# relays.net
KiCad netlist of a schematic drawn in EAGLE
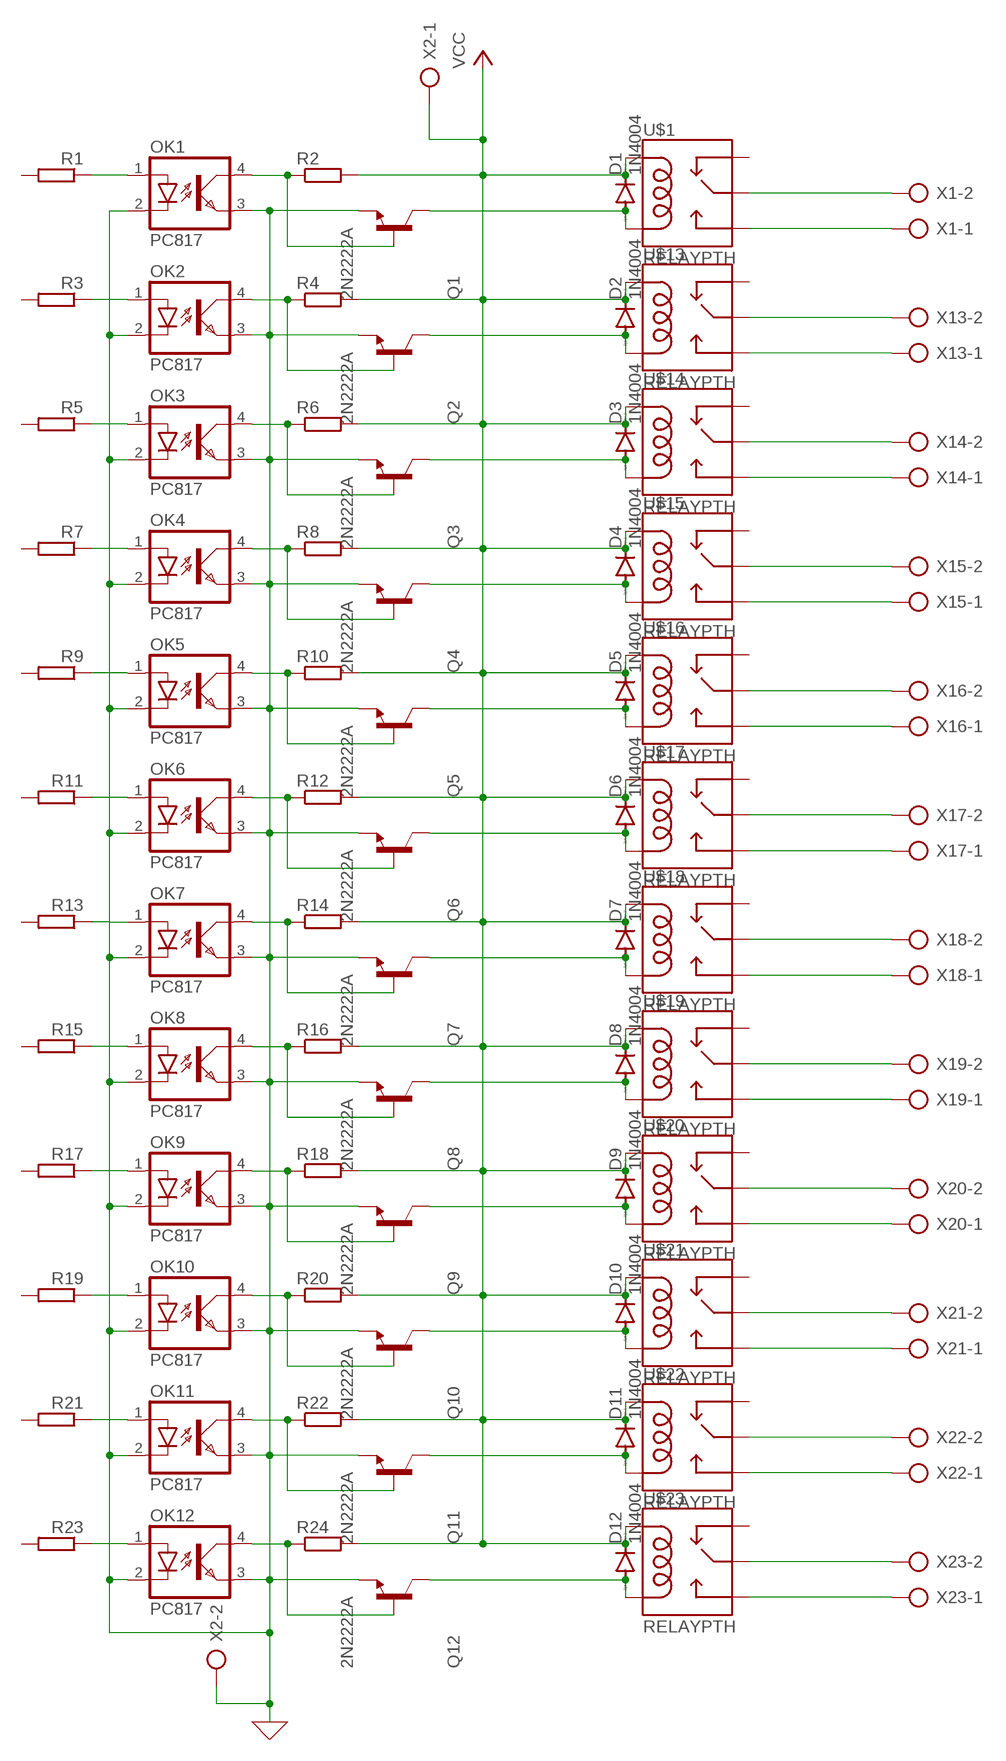
[diagram p0: schematic, sheet 1]

(export (version "E")
  (design (tool "Eeschema 10.0.6"))
  (components
    (comp (ref "D1")
      (value "1N4004")
      (footprint "eagle-import:DO41-10")
      (libsource (lib "eagle-import") (part "1N4004"))
    )
    (comp (ref "D2")
      (value "1N4004")
      (footprint "eagle-import:DO41-10")
      (libsource (lib "eagle-import") (part "1N4004"))
    )
    (comp (ref "D3")
      (value "1N4004")
      (footprint "eagle-import:DO41-10")
      (libsource (lib "eagle-import") (part "1N4004"))
    )
    (comp (ref "D4")
      (value "1N4004")
      (footprint "eagle-import:DO41-10")
      (libsource (lib "eagle-import") (part "1N4004"))
    )
    (comp (ref "D5")
      (value "1N4004")
      (footprint "eagle-import:DO41-10")
      (libsource (lib "eagle-import") (part "1N4004"))
    )
    (comp (ref "D6")
      (value "1N4004")
      (footprint "eagle-import:DO41-10")
      (libsource (lib "eagle-import") (part "1N4004"))
    )
    (comp (ref "D7")
      (value "1N4004")
      (footprint "eagle-import:DO41-10")
      (libsource (lib "eagle-import") (part "1N4004"))
    )
    (comp (ref "D8")
      (value "1N4004")
      (footprint "eagle-import:DO41-10")
      (libsource (lib "eagle-import") (part "1N4004"))
    )
    (comp (ref "D9")
      (value "1N4004")
      (footprint "eagle-import:DO41-10")
      (libsource (lib "eagle-import") (part "1N4004"))
    )
    (comp (ref "D10")
      (value "1N4004")
      (footprint "eagle-import:DO41-10")
      (libsource (lib "eagle-import") (part "1N4004"))
    )
    (comp (ref "D11")
      (value "1N4004")
      (footprint "eagle-import:DO41-10")
      (libsource (lib "eagle-import") (part "1N4004"))
    )
    (comp (ref "D12")
      (value "1N4004")
      (footprint "eagle-import:DO41-10")
      (libsource (lib "eagle-import") (part "1N4004"))
    )
    (comp (ref "OK1")
      (value "PC817")
      (footprint "eagle-import:DIL04")
      (fields (field (name "MPN") "PC817X4J000F"))
      (libsource (lib "eagle-import") (part "PC817"))
    )
    (comp (ref "OK2")
      (value "PC817")
      (footprint "eagle-import:DIL04")
      (fields (field (name "MPN") "PC817X4J000F"))
      (libsource (lib "eagle-import") (part "PC817"))
    )
    (comp (ref "OK3")
      (value "PC817")
      (footprint "eagle-import:DIL04")
      (fields (field (name "MPN") "PC817X4J000F"))
      (libsource (lib "eagle-import") (part "PC817"))
    )
    (comp (ref "OK4")
      (value "PC817")
      (footprint "eagle-import:DIL04")
      (fields (field (name "MPN") "PC817X4J000F"))
      (libsource (lib "eagle-import") (part "PC817"))
    )
    (comp (ref "OK5")
      (value "PC817")
      (footprint "eagle-import:DIL04")
      (fields (field (name "MPN") "PC817X4J000F"))
      (libsource (lib "eagle-import") (part "PC817"))
    )
    (comp (ref "OK6")
      (value "PC817")
      (footprint "eagle-import:DIL04")
      (fields (field (name "MPN") "PC817X4J000F"))
      (libsource (lib "eagle-import") (part "PC817"))
    )
    (comp (ref "OK7")
      (value "PC817")
      (footprint "eagle-import:DIL04")
      (fields (field (name "MPN") "PC817X4J000F"))
      (libsource (lib "eagle-import") (part "PC817"))
    )
    (comp (ref "OK8")
      (value "PC817")
      (footprint "eagle-import:DIL04")
      (fields (field (name "MPN") "PC817X4J000F"))
      (libsource (lib "eagle-import") (part "PC817"))
    )
    (comp (ref "OK9")
      (value "PC817")
      (footprint "eagle-import:DIL04")
      (fields (field (name "MPN") "PC817X4J000F"))
      (libsource (lib "eagle-import") (part "PC817"))
    )
    (comp (ref "OK10")
      (value "PC817")
      (footprint "eagle-import:DIL04")
      (fields (field (name "MPN") "PC817X4J000F"))
      (libsource (lib "eagle-import") (part "PC817"))
    )
    (comp (ref "OK11")
      (value "PC817")
      (footprint "eagle-import:DIL04")
      (fields (field (name "MPN") "PC817X4J000F"))
      (libsource (lib "eagle-import") (part "PC817"))
    )
    (comp (ref "OK12")
      (value "PC817")
      (footprint "eagle-import:DIL04")
      (fields (field (name "MPN") "PC817X4J000F"))
      (libsource (lib "eagle-import") (part "PC817"))
    )
    (comp (ref "Q1")
      (value "2N2222A")
      (footprint "eagle-import:TO92254P470H750-3")
      (fields (field (name "MF") "Diotec Semiconductor"))
      (libsource (lib "eagle-import") (part "2N2222A"))
    )
    (comp (ref "Q2")
      (value "2N2222A")
      (footprint "eagle-import:TO92254P470H750-3")
      (fields (field (name "MF") "Diotec Semiconductor"))
      (libsource (lib "eagle-import") (part "2N2222A"))
    )
    (comp (ref "Q3")
      (value "2N2222A")
      (footprint "eagle-import:TO92254P470H750-3")
      (fields (field (name "MF") "Diotec Semiconductor"))
      (libsource (lib "eagle-import") (part "2N2222A"))
    )
    (comp (ref "Q4")
      (value "2N2222A")
      (footprint "eagle-import:TO92254P470H750-3")
      (fields (field (name "MF") "Diotec Semiconductor"))
      (libsource (lib "eagle-import") (part "2N2222A"))
    )
    (comp (ref "Q5")
      (value "2N2222A")
      (footprint "eagle-import:TO92254P470H750-3")
      (fields (field (name "MF") "Diotec Semiconductor"))
      (libsource (lib "eagle-import") (part "2N2222A"))
    )
    (comp (ref "Q6")
      (value "2N2222A")
      (footprint "eagle-import:TO92254P470H750-3")
      (fields (field (name "MF") "Diotec Semiconductor"))
      (libsource (lib "eagle-import") (part "2N2222A"))
    )
    (comp (ref "Q7")
      (value "2N2222A")
      (footprint "eagle-import:TO92254P470H750-3")
      (fields (field (name "MF") "Diotec Semiconductor"))
      (libsource (lib "eagle-import") (part "2N2222A"))
    )
    (comp (ref "Q8")
      (value "2N2222A")
      (footprint "eagle-import:TO92254P470H750-3")
      (fields (field (name "MF") "Diotec Semiconductor"))
      (libsource (lib "eagle-import") (part "2N2222A"))
    )
    (comp (ref "Q9")
      (value "2N2222A")
      (footprint "eagle-import:TO92254P470H750-3")
      (fields (field (name "MF") "Diotec Semiconductor"))
      (libsource (lib "eagle-import") (part "2N2222A"))
    )
    (comp (ref "Q10")
      (value "2N2222A")
      (footprint "eagle-import:TO92254P470H750-3")
      (fields (field (name "MF") "Diotec Semiconductor"))
      (libsource (lib "eagle-import") (part "2N2222A"))
    )
    (comp (ref "Q11")
      (value "2N2222A")
      (footprint "eagle-import:TO92254P470H750-3")
      (fields (field (name "MF") "Diotec Semiconductor"))
      (libsource (lib "eagle-import") (part "2N2222A"))
    )
    (comp (ref "Q12")
      (value "2N2222A")
      (footprint "eagle-import:TO92254P470H750-3")
      (fields (field (name "MF") "Diotec Semiconductor"))
      (libsource (lib "eagle-import") (part "2N2222A"))
    )
    (comp (ref "R1")
      (value "R-EU_0309/12")
      (footprint "eagle-import:0309_12")
      (libsource (lib "eagle-import") (part "R-EU_0309/12"))
    )
    (comp (ref "R2")
      (value "R-EU_0309/12")
      (footprint "eagle-import:0309_12")
      (libsource (lib "eagle-import") (part "R-EU_0309/12"))
    )
    (comp (ref "R3")
      (value "R-EU_0309/12")
      (footprint "eagle-import:0309_12")
      (libsource (lib "eagle-import") (part "R-EU_0309/12"))
    )
    (comp (ref "R4")
      (value "R-EU_0309/12")
      (footprint "eagle-import:0309_12")
      (libsource (lib "eagle-import") (part "R-EU_0309/12"))
    )
    (comp (ref "R5")
      (value "R-EU_0309/12")
      (footprint "eagle-import:0309_12")
      (libsource (lib "eagle-import") (part "R-EU_0309/12"))
    )
    (comp (ref "R6")
      (value "R-EU_0309/12")
      (footprint "eagle-import:0309_12")
      (libsource (lib "eagle-import") (part "R-EU_0309/12"))
    )
    (comp (ref "R7")
      (value "R-EU_0309/12")
      (footprint "eagle-import:0309_12")
      (libsource (lib "eagle-import") (part "R-EU_0309/12"))
    )
    (comp (ref "R8")
      (value "R-EU_0309/12")
      (footprint "eagle-import:0309_12")
      (libsource (lib "eagle-import") (part "R-EU_0309/12"))
    )
    (comp (ref "R9")
      (value "R-EU_0309/12")
      (footprint "eagle-import:0309_12")
      (libsource (lib "eagle-import") (part "R-EU_0309/12"))
    )
    (comp (ref "R10")
      (value "R-EU_0309/12")
      (footprint "eagle-import:0309_12")
      (libsource (lib "eagle-import") (part "R-EU_0309/12"))
    )
    (comp (ref "R11")
      (value "R-EU_0309/12")
      (footprint "eagle-import:0309_12")
      (libsource (lib "eagle-import") (part "R-EU_0309/12"))
    )
    (comp (ref "R12")
      (value "R-EU_0309/12")
      (footprint "eagle-import:0309_12")
      (libsource (lib "eagle-import") (part "R-EU_0309/12"))
    )
    (comp (ref "R13")
      (value "R-EU_0309/12")
      (footprint "eagle-import:0309_12")
      (libsource (lib "eagle-import") (part "R-EU_0309/12"))
    )
    (comp (ref "R14")
      (value "R-EU_0309/12")
      (footprint "eagle-import:0309_12")
      (libsource (lib "eagle-import") (part "R-EU_0309/12"))
    )
    (comp (ref "R15")
      (value "R-EU_0309/12")
      (footprint "eagle-import:0309_12")
      (libsource (lib "eagle-import") (part "R-EU_0309/12"))
    )
    (comp (ref "R16")
      (value "R-EU_0309/12")
      (footprint "eagle-import:0309_12")
      (libsource (lib "eagle-import") (part "R-EU_0309/12"))
    )
    (comp (ref "R17")
      (value "R-EU_0309/12")
      (footprint "eagle-import:0309_12")
      (libsource (lib "eagle-import") (part "R-EU_0309/12"))
    )
    (comp (ref "R18")
      (value "R-EU_0309/12")
      (footprint "eagle-import:0309_12")
      (libsource (lib "eagle-import") (part "R-EU_0309/12"))
    )
    (comp (ref "R19")
      (value "R-EU_0309/12")
      (footprint "eagle-import:0309_12")
      (libsource (lib "eagle-import") (part "R-EU_0309/12"))
    )
    (comp (ref "R20")
      (value "R-EU_0309/12")
      (footprint "eagle-import:0309_12")
      (libsource (lib "eagle-import") (part "R-EU_0309/12"))
    )
    (comp (ref "R21")
      (value "R-EU_0309/12")
      (footprint "eagle-import:0309_12")
      (libsource (lib "eagle-import") (part "R-EU_0309/12"))
    )
    (comp (ref "R22")
      (value "R-EU_0309/12")
      (footprint "eagle-import:0309_12")
      (libsource (lib "eagle-import") (part "R-EU_0309/12"))
    )
    (comp (ref "R23")
      (value "R-EU_0309/12")
      (footprint "eagle-import:0309_12")
      (libsource (lib "eagle-import") (part "R-EU_0309/12"))
    )
    (comp (ref "R24")
      (value "R-EU_0309/12")
      (footprint "eagle-import:0309_12")
      (libsource (lib "eagle-import") (part "R-EU_0309/12"))
    )
    (comp (ref "U$1")
      (value "RELAYPTH")
      (footprint "eagle-import:SRD-05VDC-SL-C")
      (libsource (lib "eagle-import") (part "RELAYPTH"))
    )
    (comp (ref "U$13")
      (value "RELAYPTH")
      (footprint "eagle-import:SRD-05VDC-SL-C")
      (libsource (lib "eagle-import") (part "RELAYPTH"))
    )
    (comp (ref "U$14")
      (value "RELAYPTH")
      (footprint "eagle-import:SRD-05VDC-SL-C")
      (libsource (lib "eagle-import") (part "RELAYPTH"))
    )
    (comp (ref "U$15")
      (value "RELAYPTH")
      (footprint "eagle-import:SRD-05VDC-SL-C")
      (libsource (lib "eagle-import") (part "RELAYPTH"))
    )
    (comp (ref "U$16")
      (value "RELAYPTH")
      (footprint "eagle-import:SRD-05VDC-SL-C")
      (libsource (lib "eagle-import") (part "RELAYPTH"))
    )
    (comp (ref "U$17")
      (value "RELAYPTH")
      (footprint "eagle-import:SRD-05VDC-SL-C")
      (libsource (lib "eagle-import") (part "RELAYPTH"))
    )
    (comp (ref "U$18")
      (value "RELAYPTH")
      (footprint "eagle-import:SRD-05VDC-SL-C")
      (libsource (lib "eagle-import") (part "RELAYPTH"))
    )
    (comp (ref "U$19")
      (value "RELAYPTH")
      (footprint "eagle-import:SRD-05VDC-SL-C")
      (libsource (lib "eagle-import") (part "RELAYPTH"))
    )
    (comp (ref "U$20")
      (value "RELAYPTH")
      (footprint "eagle-import:SRD-05VDC-SL-C")
      (libsource (lib "eagle-import") (part "RELAYPTH"))
    )
    (comp (ref "U$21")
      (value "RELAYPTH")
      (footprint "eagle-import:SRD-05VDC-SL-C")
      (libsource (lib "eagle-import") (part "RELAYPTH"))
    )
    (comp (ref "U$22")
      (value "RELAYPTH")
      (footprint "eagle-import:SRD-05VDC-SL-C")
      (libsource (lib "eagle-import") (part "RELAYPTH"))
    )
    (comp (ref "U$23")
      (value "RELAYPTH")
      (footprint "eagle-import:SRD-05VDC-SL-C")
      (libsource (lib "eagle-import") (part "RELAYPTH"))
    )
    (comp (ref "X1")
      (value "AK500/2-H")
      (footprint "eagle-import:AK500_2-H")
      (libsource (lib "eagle-import") (part "AK500/2-H"))
    )
    (comp (ref "X2")
      (value "AK500/2-H")
      (footprint "eagle-import:AK500_2-H")
      (libsource (lib "eagle-import") (part "AK500/2-H"))
    )
    (comp (ref "X13")
      (value "AK500/2-H")
      (footprint "eagle-import:AK500_2-H")
      (libsource (lib "eagle-import") (part "AK500/2-H"))
    )
    (comp (ref "X14")
      (value "AK500/2-H")
      (footprint "eagle-import:AK500_2-H")
      (libsource (lib "eagle-import") (part "AK500/2-H"))
    )
    (comp (ref "X15")
      (value "AK500/2-H")
      (footprint "eagle-import:AK500_2-H")
      (libsource (lib "eagle-import") (part "AK500/2-H"))
    )
    (comp (ref "X16")
      (value "AK500/2-H")
      (footprint "eagle-import:AK500_2-H")
      (libsource (lib "eagle-import") (part "AK500/2-H"))
    )
    (comp (ref "X17")
      (value "AK500/2-H")
      (footprint "eagle-import:AK500_2-H")
      (libsource (lib "eagle-import") (part "AK500/2-H"))
    )
    (comp (ref "X18")
      (value "AK500/2-H")
      (footprint "eagle-import:AK500_2-H")
      (libsource (lib "eagle-import") (part "AK500/2-H"))
    )
    (comp (ref "X19")
      (value "AK500/2-H")
      (footprint "eagle-import:AK500_2-H")
      (libsource (lib "eagle-import") (part "AK500/2-H"))
    )
    (comp (ref "X20")
      (value "AK500/2-H")
      (footprint "eagle-import:AK500_2-H")
      (libsource (lib "eagle-import") (part "AK500/2-H"))
    )
    (comp (ref "X21")
      (value "AK500/2-H")
      (footprint "eagle-import:AK500_2-H")
      (libsource (lib "eagle-import") (part "AK500/2-H"))
    )
    (comp (ref "X22")
      (value "AK500/2-H")
      (footprint "eagle-import:AK500_2-H")
      (libsource (lib "eagle-import") (part "AK500/2-H"))
    )
    (comp (ref "X23")
      (value "AK500/2-H")
      (footprint "eagle-import:AK500_2-H")
      (libsource (lib "eagle-import") (part "AK500/2-H"))
    )
  )
  (nets
    (net (code "1") (name "GND") (class "Default")
      (node (ref "OK1") (pin "2") (pinfunction "C_2") (pintype "passive"))
      (node (ref "OK1") (pin "3") (pinfunction "EMIT_3") (pintype "passive"))
      (node (ref "OK10") (pin "2") (pinfunction "C_2") (pintype "passive"))
      (node (ref "OK10") (pin "3") (pinfunction "EMIT_3") (pintype "passive"))
      (node (ref "OK11") (pin "2") (pinfunction "C_2") (pintype "passive"))
      (node (ref "OK11") (pin "3") (pinfunction "EMIT_3") (pintype "passive"))
      (node (ref "OK12") (pin "2") (pinfunction "C_2") (pintype "passive"))
      (node (ref "OK12") (pin "3") (pinfunction "EMIT_3") (pintype "passive"))
      (node (ref "OK2") (pin "2") (pinfunction "C_2") (pintype "passive"))
      (node (ref "OK2") (pin "3") (pinfunction "EMIT_3") (pintype "passive"))
      (node (ref "OK3") (pin "2") (pinfunction "C_2") (pintype "passive"))
      (node (ref "OK3") (pin "3") (pinfunction "EMIT_3") (pintype "passive"))
      (node (ref "OK4") (pin "2") (pinfunction "C_2") (pintype "passive"))
      (node (ref "OK4") (pin "3") (pinfunction "EMIT_3") (pintype "passive"))
      (node (ref "OK5") (pin "2") (pinfunction "C_2") (pintype "passive"))
      (node (ref "OK5") (pin "3") (pinfunction "EMIT_3") (pintype "passive"))
      (node (ref "OK6") (pin "2") (pinfunction "C_2") (pintype "passive"))
      (node (ref "OK6") (pin "3") (pinfunction "EMIT_3") (pintype "passive"))
      (node (ref "OK7") (pin "2") (pinfunction "C_2") (pintype "passive"))
      (node (ref "OK7") (pin "3") (pinfunction "EMIT_3") (pintype "passive"))
      (node (ref "OK8") (pin "2") (pinfunction "C_2") (pintype "passive"))
      (node (ref "OK8") (pin "3") (pinfunction "EMIT_3") (pintype "passive"))
      (node (ref "OK9") (pin "2") (pinfunction "C_2") (pintype "passive"))
      (node (ref "OK9") (pin "3") (pinfunction "EMIT_3") (pintype "passive"))
      (node (ref "Q1") (pin "1") (pinfunction "E_1") (pintype "passive"))
      (node (ref "Q10") (pin "1") (pinfunction "E_1") (pintype "passive"))
      (node (ref "Q11") (pin "1") (pinfunction "E_1") (pintype "passive"))
      (node (ref "Q12") (pin "1") (pinfunction "E_1") (pintype "passive"))
      (node (ref "Q2") (pin "1") (pinfunction "E_1") (pintype "passive"))
      (node (ref "Q3") (pin "1") (pinfunction "E_1") (pintype "passive"))
      (node (ref "Q4") (pin "1") (pinfunction "E_1") (pintype "passive"))
      (node (ref "Q5") (pin "1") (pinfunction "E_1") (pintype "passive"))
      (node (ref "Q6") (pin "1") (pinfunction "E_1") (pintype "passive"))
      (node (ref "Q7") (pin "1") (pinfunction "E_1") (pintype "passive"))
      (node (ref "Q8") (pin "1") (pinfunction "E_1") (pintype "passive"))
      (node (ref "Q9") (pin "1") (pinfunction "E_1") (pintype "passive"))
      (node (ref "X2") (pin "2") (pinfunction "KL_2") (pintype "passive"))
    )
    (net (code "2") (name "Net-(OK1-A)") (class "Default")
      (node (ref "OK1") (pin "1") (pinfunction "A_1") (pintype "passive"))
      (node (ref "R1") (pin "1") (pinfunction "1_1") (pintype "passive"))
    )
    (net (code "3") (name "Net-(OK1-COL)") (class "Default")
      (node (ref "OK1") (pin "4") (pinfunction "COL_4") (pintype "passive"))
      (node (ref "Q1") (pin "2") (pinfunction "B_2") (pintype "passive"))
      (node (ref "R2") (pin "1") (pinfunction "1_1") (pintype "passive"))
    )
    (net (code "4") (name "Net-(OK2-A)") (class "Default")
      (node (ref "OK2") (pin "1") (pinfunction "A_1") (pintype "passive"))
      (node (ref "R3") (pin "1") (pinfunction "1_1") (pintype "passive"))
    )
    (net (code "5") (name "Net-(OK2-COL)") (class "Default")
      (node (ref "OK2") (pin "4") (pinfunction "COL_4") (pintype "passive"))
      (node (ref "Q2") (pin "2") (pinfunction "B_2") (pintype "passive"))
      (node (ref "R4") (pin "1") (pinfunction "1_1") (pintype "passive"))
    )
    (net (code "6") (name "Net-(OK3-A)") (class "Default")
      (node (ref "OK3") (pin "1") (pinfunction "A_1") (pintype "passive"))
      (node (ref "R5") (pin "1") (pinfunction "1_1") (pintype "passive"))
    )
    (net (code "7") (name "Net-(OK3-COL)") (class "Default")
      (node (ref "OK3") (pin "4") (pinfunction "COL_4") (pintype "passive"))
      (node (ref "Q3") (pin "2") (pinfunction "B_2") (pintype "passive"))
      (node (ref "R6") (pin "1") (pinfunction "1_1") (pintype "passive"))
    )
    (net (code "8") (name "Net-(OK4-A)") (class "Default")
      (node (ref "OK4") (pin "1") (pinfunction "A_1") (pintype "passive"))
      (node (ref "R7") (pin "1") (pinfunction "1_1") (pintype "passive"))
    )
    (net (code "9") (name "Net-(OK4-COL)") (class "Default")
      (node (ref "OK4") (pin "4") (pinfunction "COL_4") (pintype "passive"))
      (node (ref "Q4") (pin "2") (pinfunction "B_2") (pintype "passive"))
      (node (ref "R8") (pin "1") (pinfunction "1_1") (pintype "passive"))
    )
    (net (code "10") (name "Net-(OK5-A)") (class "Default")
      (node (ref "OK5") (pin "1") (pinfunction "A_1") (pintype "passive"))
      (node (ref "R9") (pin "1") (pinfunction "1_1") (pintype "passive"))
    )
    (net (code "11") (name "Net-(OK5-COL)") (class "Default")
      (node (ref "OK5") (pin "4") (pinfunction "COL_4") (pintype "passive"))
      (node (ref "Q5") (pin "2") (pinfunction "B_2") (pintype "passive"))
      (node (ref "R10") (pin "1") (pinfunction "1_1") (pintype "passive"))
    )
    (net (code "12") (name "Net-(OK6-A)") (class "Default")
      (node (ref "OK6") (pin "1") (pinfunction "A_1") (pintype "passive"))
      (node (ref "R11") (pin "1") (pinfunction "1_1") (pintype "passive"))
    )
    (net (code "13") (name "Net-(OK6-COL)") (class "Default")
      (node (ref "OK6") (pin "4") (pinfunction "COL_4") (pintype "passive"))
      (node (ref "Q6") (pin "2") (pinfunction "B_2") (pintype "passive"))
      (node (ref "R12") (pin "1") (pinfunction "1_1") (pintype "passive"))
    )
    (net (code "14") (name "Net-(OK7-A)") (class "Default")
      (node (ref "OK7") (pin "1") (pinfunction "A_1") (pintype "passive"))
      (node (ref "R13") (pin "1") (pinfunction "1_1") (pintype "passive"))
    )
    (net (code "15") (name "Net-(OK7-COL)") (class "Default")
      (node (ref "OK7") (pin "4") (pinfunction "COL_4") (pintype "passive"))
      (node (ref "Q7") (pin "2") (pinfunction "B_2") (pintype "passive"))
      (node (ref "R14") (pin "1") (pinfunction "1_1") (pintype "passive"))
    )
    (net (code "16") (name "Net-(OK8-A)") (class "Default")
      (node (ref "OK8") (pin "1") (pinfunction "A_1") (pintype "passive"))
      (node (ref "R15") (pin "1") (pinfunction "1_1") (pintype "passive"))
    )
    (net (code "17") (name "Net-(OK8-COL)") (class "Default")
      (node (ref "OK8") (pin "4") (pinfunction "COL_4") (pintype "passive"))
      (node (ref "Q8") (pin "2") (pinfunction "B_2") (pintype "passive"))
      (node (ref "R16") (pin "1") (pinfunction "1_1") (pintype "passive"))
    )
    (net (code "18") (name "Net-(OK9-A)") (class "Default")
      (node (ref "OK9") (pin "1") (pinfunction "A_1") (pintype "passive"))
      (node (ref "R17") (pin "1") (pinfunction "1_1") (pintype "passive"))
    )
    (net (code "19") (name "Net-(OK9-COL)") (class "Default")
      (node (ref "OK9") (pin "4") (pinfunction "COL_4") (pintype "passive"))
      (node (ref "Q9") (pin "2") (pinfunction "B_2") (pintype "passive"))
      (node (ref "R18") (pin "1") (pinfunction "1_1") (pintype "passive"))
    )
    (net (code "20") (name "Net-(OK10-A)") (class "Default")
      (node (ref "OK10") (pin "1") (pinfunction "A_1") (pintype "passive"))
      (node (ref "R19") (pin "1") (pinfunction "1_1") (pintype "passive"))
    )
    (net (code "21") (name "Net-(OK10-COL)") (class "Default")
      (node (ref "OK10") (pin "4") (pinfunction "COL_4") (pintype "passive"))
      (node (ref "Q10") (pin "2") (pinfunction "B_2") (pintype "passive"))
      (node (ref "R20") (pin "1") (pinfunction "1_1") (pintype "passive"))
    )
    (net (code "22") (name "Net-(OK11-A)") (class "Default")
      (node (ref "OK11") (pin "1") (pinfunction "A_1") (pintype "passive"))
      (node (ref "R21") (pin "1") (pinfunction "1_1") (pintype "passive"))
    )
    (net (code "23") (name "Net-(OK11-COL)") (class "Default")
      (node (ref "OK11") (pin "4") (pinfunction "COL_4") (pintype "passive"))
      (node (ref "Q11") (pin "2") (pinfunction "B_2") (pintype "passive"))
      (node (ref "R22") (pin "1") (pinfunction "1_1") (pintype "passive"))
    )
    (net (code "24") (name "Net-(OK12-A)") (class "Default")
      (node (ref "OK12") (pin "1") (pinfunction "A_1") (pintype "passive"))
      (node (ref "R23") (pin "1") (pinfunction "1_1") (pintype "passive"))
    )
    (net (code "25") (name "Net-(OK12-COL)") (class "Default")
      (node (ref "OK12") (pin "4") (pinfunction "COL_4") (pintype "passive"))
      (node (ref "Q12") (pin "2") (pinfunction "B_2") (pintype "passive"))
      (node (ref "R24") (pin "1") (pinfunction "1_1") (pintype "passive"))
    )
    (net (code "26") (name "Net-(Q1-C)") (class "Default")
      (node (ref "D1") (pin "A") (pinfunction "A_A") (pintype "passive"))
      (node (ref "Q1") (pin "3") (pinfunction "C_3") (pintype "passive"))
      (node (ref "U$1") (pin "COIL0") (pinfunction "COIL0_COIL0") (pintype "bidirectional"))
    )
    (net (code "27") (name "Net-(Q2-C)") (class "Default")
      (node (ref "D2") (pin "A") (pinfunction "A_A") (pintype "passive"))
      (node (ref "Q2") (pin "3") (pinfunction "C_3") (pintype "passive"))
      (node (ref "U$13") (pin "COIL0") (pinfunction "COIL0_COIL0") (pintype "bidirectional"))
    )
    (net (code "28") (name "Net-(Q3-C)") (class "Default")
      (node (ref "D3") (pin "A") (pinfunction "A_A") (pintype "passive"))
      (node (ref "Q3") (pin "3") (pinfunction "C_3") (pintype "passive"))
      (node (ref "U$14") (pin "COIL0") (pinfunction "COIL0_COIL0") (pintype "bidirectional"))
    )
    (net (code "29") (name "Net-(Q4-C)") (class "Default")
      (node (ref "D4") (pin "A") (pinfunction "A_A") (pintype "passive"))
      (node (ref "Q4") (pin "3") (pinfunction "C_3") (pintype "passive"))
      (node (ref "U$15") (pin "COIL0") (pinfunction "COIL0_COIL0") (pintype "bidirectional"))
    )
    (net (code "30") (name "Net-(Q5-C)") (class "Default")
      (node (ref "D5") (pin "A") (pinfunction "A_A") (pintype "passive"))
      (node (ref "Q5") (pin "3") (pinfunction "C_3") (pintype "passive"))
      (node (ref "U$16") (pin "COIL0") (pinfunction "COIL0_COIL0") (pintype "bidirectional"))
    )
    (net (code "31") (name "Net-(Q6-C)") (class "Default")
      (node (ref "D6") (pin "A") (pinfunction "A_A") (pintype "passive"))
      (node (ref "Q6") (pin "3") (pinfunction "C_3") (pintype "passive"))
      (node (ref "U$17") (pin "COIL0") (pinfunction "COIL0_COIL0") (pintype "bidirectional"))
    )
    (net (code "32") (name "Net-(Q7-C)") (class "Default")
      (node (ref "D7") (pin "A") (pinfunction "A_A") (pintype "passive"))
      (node (ref "Q7") (pin "3") (pinfunction "C_3") (pintype "passive"))
      (node (ref "U$18") (pin "COIL0") (pinfunction "COIL0_COIL0") (pintype "bidirectional"))
    )
    (net (code "33") (name "Net-(Q8-C)") (class "Default")
      (node (ref "D8") (pin "A") (pinfunction "A_A") (pintype "passive"))
      (node (ref "Q8") (pin "3") (pinfunction "C_3") (pintype "passive"))
      (node (ref "U$19") (pin "COIL0") (pinfunction "COIL0_COIL0") (pintype "bidirectional"))
    )
    (net (code "34") (name "Net-(Q9-C)") (class "Default")
      (node (ref "D9") (pin "A") (pinfunction "A_A") (pintype "passive"))
      (node (ref "Q9") (pin "3") (pinfunction "C_3") (pintype "passive"))
      (node (ref "U$20") (pin "COIL0") (pinfunction "COIL0_COIL0") (pintype "bidirectional"))
    )
    (net (code "35") (name "Net-(Q10-C)") (class "Default")
      (node (ref "D10") (pin "A") (pinfunction "A_A") (pintype "passive"))
      (node (ref "Q10") (pin "3") (pinfunction "C_3") (pintype "passive"))
      (node (ref "U$21") (pin "COIL0") (pinfunction "COIL0_COIL0") (pintype "bidirectional"))
    )
    (net (code "36") (name "Net-(Q11-C)") (class "Default")
      (node (ref "D11") (pin "A") (pinfunction "A_A") (pintype "passive"))
      (node (ref "Q11") (pin "3") (pinfunction "C_3") (pintype "passive"))
      (node (ref "U$22") (pin "COIL0") (pinfunction "COIL0_COIL0") (pintype "bidirectional"))
    )
    (net (code "37") (name "Net-(Q12-C)") (class "Default")
      (node (ref "D12") (pin "A") (pinfunction "A_A") (pintype "passive"))
      (node (ref "Q12") (pin "3") (pinfunction "C_3") (pintype "passive"))
      (node (ref "U$23") (pin "COIL0") (pinfunction "COIL0_COIL0") (pintype "bidirectional"))
    )
    (net (code "38") (name "Net-(X1A-KL)") (class "Default")
      (node (ref "U$1") (pin "SWOPEN") (pinfunction "SWOPEN_SWOPEN") (pintype "bidirectional"))
      (node (ref "X1") (pin "1") (pinfunction "KL_1") (pintype "passive"))
    )
    (net (code "39") (name "Net-(X1B-KL)") (class "Default")
      (node (ref "U$1") (pin "SWCOMMON") (pinfunction "SWCOMMON_SWCOMMON") (pintype "bidirectional"))
      (node (ref "X1") (pin "2") (pinfunction "KL_2") (pintype "passive"))
    )
    (net (code "40") (name "Net-(X13A-KL)") (class "Default")
      (node (ref "U$13") (pin "SWOPEN") (pinfunction "SWOPEN_SWOPEN") (pintype "bidirectional"))
      (node (ref "X13") (pin "1") (pinfunction "KL_1") (pintype "passive"))
    )
    (net (code "41") (name "Net-(X13B-KL)") (class "Default")
      (node (ref "U$13") (pin "SWCOMMON") (pinfunction "SWCOMMON_SWCOMMON") (pintype "bidirectional"))
      (node (ref "X13") (pin "2") (pinfunction "KL_2") (pintype "passive"))
    )
    (net (code "42") (name "Net-(X14A-KL)") (class "Default")
      (node (ref "U$14") (pin "SWOPEN") (pinfunction "SWOPEN_SWOPEN") (pintype "bidirectional"))
      (node (ref "X14") (pin "1") (pinfunction "KL_1") (pintype "passive"))
    )
    (net (code "43") (name "Net-(X14B-KL)") (class "Default")
      (node (ref "U$14") (pin "SWCOMMON") (pinfunction "SWCOMMON_SWCOMMON") (pintype "bidirectional"))
      (node (ref "X14") (pin "2") (pinfunction "KL_2") (pintype "passive"))
    )
    (net (code "44") (name "Net-(X15A-KL)") (class "Default")
      (node (ref "U$15") (pin "SWOPEN") (pinfunction "SWOPEN_SWOPEN") (pintype "bidirectional"))
      (node (ref "X15") (pin "1") (pinfunction "KL_1") (pintype "passive"))
    )
    (net (code "45") (name "Net-(X15B-KL)") (class "Default")
      (node (ref "U$15") (pin "SWCOMMON") (pinfunction "SWCOMMON_SWCOMMON") (pintype "bidirectional"))
      (node (ref "X15") (pin "2") (pinfunction "KL_2") (pintype "passive"))
    )
    (net (code "46") (name "Net-(X16A-KL)") (class "Default")
      (node (ref "U$16") (pin "SWOPEN") (pinfunction "SWOPEN_SWOPEN") (pintype "bidirectional"))
      (node (ref "X16") (pin "1") (pinfunction "KL_1") (pintype "passive"))
    )
    (net (code "47") (name "Net-(X16B-KL)") (class "Default")
      (node (ref "U$16") (pin "SWCOMMON") (pinfunction "SWCOMMON_SWCOMMON") (pintype "bidirectional"))
      (node (ref "X16") (pin "2") (pinfunction "KL_2") (pintype "passive"))
    )
    (net (code "48") (name "Net-(X17A-KL)") (class "Default")
      (node (ref "U$17") (pin "SWOPEN") (pinfunction "SWOPEN_SWOPEN") (pintype "bidirectional"))
      (node (ref "X17") (pin "1") (pinfunction "KL_1") (pintype "passive"))
    )
    (net (code "49") (name "Net-(X17B-KL)") (class "Default")
      (node (ref "U$17") (pin "SWCOMMON") (pinfunction "SWCOMMON_SWCOMMON") (pintype "bidirectional"))
      (node (ref "X17") (pin "2") (pinfunction "KL_2") (pintype "passive"))
    )
    (net (code "50") (name "Net-(X18A-KL)") (class "Default")
      (node (ref "U$18") (pin "SWOPEN") (pinfunction "SWOPEN_SWOPEN") (pintype "bidirectional"))
      (node (ref "X18") (pin "1") (pinfunction "KL_1") (pintype "passive"))
    )
    (net (code "51") (name "Net-(X18B-KL)") (class "Default")
      (node (ref "U$18") (pin "SWCOMMON") (pinfunction "SWCOMMON_SWCOMMON") (pintype "bidirectional"))
      (node (ref "X18") (pin "2") (pinfunction "KL_2") (pintype "passive"))
    )
    (net (code "52") (name "Net-(X19A-KL)") (class "Default")
      (node (ref "U$19") (pin "SWOPEN") (pinfunction "SWOPEN_SWOPEN") (pintype "bidirectional"))
      (node (ref "X19") (pin "1") (pinfunction "KL_1") (pintype "passive"))
    )
    (net (code "53") (name "Net-(X19B-KL)") (class "Default")
      (node (ref "U$19") (pin "SWCOMMON") (pinfunction "SWCOMMON_SWCOMMON") (pintype "bidirectional"))
      (node (ref "X19") (pin "2") (pinfunction "KL_2") (pintype "passive"))
    )
    (net (code "54") (name "Net-(X20A-KL)") (class "Default")
      (node (ref "U$20") (pin "SWOPEN") (pinfunction "SWOPEN_SWOPEN") (pintype "bidirectional"))
      (node (ref "X20") (pin "1") (pinfunction "KL_1") (pintype "passive"))
    )
    (net (code "55") (name "Net-(X20B-KL)") (class "Default")
      (node (ref "U$20") (pin "SWCOMMON") (pinfunction "SWCOMMON_SWCOMMON") (pintype "bidirectional"))
      (node (ref "X20") (pin "2") (pinfunction "KL_2") (pintype "passive"))
    )
    (net (code "56") (name "Net-(X21A-KL)") (class "Default")
      (node (ref "U$21") (pin "SWOPEN") (pinfunction "SWOPEN_SWOPEN") (pintype "bidirectional"))
      (node (ref "X21") (pin "1") (pinfunction "KL_1") (pintype "passive"))
    )
    (net (code "57") (name "Net-(X21B-KL)") (class "Default")
      (node (ref "U$21") (pin "SWCOMMON") (pinfunction "SWCOMMON_SWCOMMON") (pintype "bidirectional"))
      (node (ref "X21") (pin "2") (pinfunction "KL_2") (pintype "passive"))
    )
    (net (code "58") (name "Net-(X22A-KL)") (class "Default")
      (node (ref "U$22") (pin "SWOPEN") (pinfunction "SWOPEN_SWOPEN") (pintype "bidirectional"))
      (node (ref "X22") (pin "1") (pinfunction "KL_1") (pintype "passive"))
    )
    (net (code "59") (name "Net-(X22B-KL)") (class "Default")
      (node (ref "U$22") (pin "SWCOMMON") (pinfunction "SWCOMMON_SWCOMMON") (pintype "bidirectional"))
      (node (ref "X22") (pin "2") (pinfunction "KL_2") (pintype "passive"))
    )
    (net (code "60") (name "Net-(X23A-KL)") (class "Default")
      (node (ref "U$23") (pin "SWOPEN") (pinfunction "SWOPEN_SWOPEN") (pintype "bidirectional"))
      (node (ref "X23") (pin "1") (pinfunction "KL_1") (pintype "passive"))
    )
    (net (code "61") (name "Net-(X23B-KL)") (class "Default")
      (node (ref "U$23") (pin "SWCOMMON") (pinfunction "SWCOMMON_SWCOMMON") (pintype "bidirectional"))
      (node (ref "X23") (pin "2") (pinfunction "KL_2") (pintype "passive"))
    )
    (net (code "62") (name "VCC") (class "Default")
      (node (ref "D1") (pin "C") (pinfunction "C_C") (pintype "passive"))
      (node (ref "D10") (pin "C") (pinfunction "C_C") (pintype "passive"))
      (node (ref "D11") (pin "C") (pinfunction "C_C") (pintype "passive"))
      (node (ref "D12") (pin "C") (pinfunction "C_C") (pintype "passive"))
      (node (ref "D2") (pin "C") (pinfunction "C_C") (pintype "passive"))
      (node (ref "D3") (pin "C") (pinfunction "C_C") (pintype "passive"))
      (node (ref "D4") (pin "C") (pinfunction "C_C") (pintype "passive"))
      (node (ref "D5") (pin "C") (pinfunction "C_C") (pintype "passive"))
      (node (ref "D6") (pin "C") (pinfunction "C_C") (pintype "passive"))
      (node (ref "D7") (pin "C") (pinfunction "C_C") (pintype "passive"))
      (node (ref "D8") (pin "C") (pinfunction "C_C") (pintype "passive"))
      (node (ref "D9") (pin "C") (pinfunction "C_C") (pintype "passive"))
      (node (ref "R10") (pin "2") (pinfunction "2_2") (pintype "passive"))
      (node (ref "R12") (pin "2") (pinfunction "2_2") (pintype "passive"))
      (node (ref "R14") (pin "2") (pinfunction "2_2") (pintype "passive"))
      (node (ref "R16") (pin "2") (pinfunction "2_2") (pintype "passive"))
      (node (ref "R18") (pin "2") (pinfunction "2_2") (pintype "passive"))
      (node (ref "R2") (pin "2") (pinfunction "2_2") (pintype "passive"))
      (node (ref "R20") (pin "2") (pinfunction "2_2") (pintype "passive"))
      (node (ref "R22") (pin "2") (pinfunction "2_2") (pintype "passive"))
      (node (ref "R24") (pin "2") (pinfunction "2_2") (pintype "passive"))
      (node (ref "R4") (pin "2") (pinfunction "2_2") (pintype "passive"))
      (node (ref "R6") (pin "2") (pinfunction "2_2") (pintype "passive"))
      (node (ref "R8") (pin "2") (pinfunction "2_2") (pintype "passive"))
      (node (ref "U$1") (pin "COIL1") (pinfunction "COIL1_COIL1") (pintype "bidirectional"))
      (node (ref "U$13") (pin "COIL1") (pinfunction "COIL1_COIL1") (pintype "bidirectional"))
      (node (ref "U$14") (pin "COIL1") (pinfunction "COIL1_COIL1") (pintype "bidirectional"))
      (node (ref "U$15") (pin "COIL1") (pinfunction "COIL1_COIL1") (pintype "bidirectional"))
      (node (ref "U$16") (pin "COIL1") (pinfunction "COIL1_COIL1") (pintype "bidirectional"))
      (node (ref "U$17") (pin "COIL1") (pinfunction "COIL1_COIL1") (pintype "bidirectional"))
      (node (ref "U$18") (pin "COIL1") (pinfunction "COIL1_COIL1") (pintype "bidirectional"))
      (node (ref "U$19") (pin "COIL1") (pinfunction "COIL1_COIL1") (pintype "bidirectional"))
      (node (ref "U$20") (pin "COIL1") (pinfunction "COIL1_COIL1") (pintype "bidirectional"))
      (node (ref "U$21") (pin "COIL1") (pinfunction "COIL1_COIL1") (pintype "bidirectional"))
      (node (ref "U$22") (pin "COIL1") (pinfunction "COIL1_COIL1") (pintype "bidirectional"))
      (node (ref "U$23") (pin "COIL1") (pinfunction "COIL1_COIL1") (pintype "bidirectional"))
      (node (ref "X2") (pin "1") (pinfunction "KL_1") (pintype "passive"))
    )
    (net (code "63") (name "unconnected-(R1-Pad2)") (class "Default")
      (node (ref "R1") (pin "2") (pinfunction "2_2") (pintype "passive"))
    )
    (net (code "64") (name "unconnected-(R3-Pad2)") (class "Default")
      (node (ref "R3") (pin "2") (pinfunction "2_2") (pintype "passive"))
    )
    (net (code "65") (name "unconnected-(R5-Pad2)") (class "Default")
      (node (ref "R5") (pin "2") (pinfunction "2_2") (pintype "passive"))
    )
    (net (code "66") (name "unconnected-(R7-Pad2)") (class "Default")
      (node (ref "R7") (pin "2") (pinfunction "2_2") (pintype "passive"))
    )
    (net (code "67") (name "unconnected-(R9-Pad2)") (class "Default")
      (node (ref "R9") (pin "2") (pinfunction "2_2") (pintype "passive"))
    )
    (net (code "68") (name "unconnected-(R11-Pad2)") (class "Default")
      (node (ref "R11") (pin "2") (pinfunction "2_2") (pintype "passive"))
    )
    (net (code "69") (name "unconnected-(R13-Pad2)") (class "Default")
      (node (ref "R13") (pin "2") (pinfunction "2_2") (pintype "passive"))
    )
    (net (code "70") (name "unconnected-(R15-Pad2)") (class "Default")
      (node (ref "R15") (pin "2") (pinfunction "2_2") (pintype "passive"))
    )
    (net (code "71") (name "unconnected-(R17-Pad2)") (class "Default")
      (node (ref "R17") (pin "2") (pinfunction "2_2") (pintype "passive"))
    )
    (net (code "72") (name "unconnected-(R19-Pad2)") (class "Default")
      (node (ref "R19") (pin "2") (pinfunction "2_2") (pintype "passive"))
    )
    (net (code "73") (name "unconnected-(R21-Pad2)") (class "Default")
      (node (ref "R21") (pin "2") (pinfunction "2_2") (pintype "passive"))
    )
    (net (code "74") (name "unconnected-(R23-Pad2)") (class "Default")
      (node (ref "R23") (pin "2") (pinfunction "2_2") (pintype "passive"))
    )
    (net (code "75") (name "unconnected-(U$1-SWCLOSE-PadSWCLOSED)") (class "Default")
      (node (ref "U$1") (pin "SWCLOSED") (pinfunction "SWCLOSE_SWCLOSED") (pintype "bidirectional"))
    )
    (net (code "76") (name "unconnected-(U$13-SWCLOSE-PadSWCLOSED)") (class "Default")
      (node (ref "U$13") (pin "SWCLOSED") (pinfunction "SWCLOSE_SWCLOSED") (pintype "bidirectional"))
    )
    (net (code "77") (name "unconnected-(U$14-SWCLOSE-PadSWCLOSED)") (class "Default")
      (node (ref "U$14") (pin "SWCLOSED") (pinfunction "SWCLOSE_SWCLOSED") (pintype "bidirectional"))
    )
    (net (code "78") (name "unconnected-(U$15-SWCLOSE-PadSWCLOSED)") (class "Default")
      (node (ref "U$15") (pin "SWCLOSED") (pinfunction "SWCLOSE_SWCLOSED") (pintype "bidirectional"))
    )
    (net (code "79") (name "unconnected-(U$16-SWCLOSE-PadSWCLOSED)") (class "Default")
      (node (ref "U$16") (pin "SWCLOSED") (pinfunction "SWCLOSE_SWCLOSED") (pintype "bidirectional"))
    )
    (net (code "80") (name "unconnected-(U$17-SWCLOSE-PadSWCLOSED)") (class "Default")
      (node (ref "U$17") (pin "SWCLOSED") (pinfunction "SWCLOSE_SWCLOSED") (pintype "bidirectional"))
    )
    (net (code "81") (name "unconnected-(U$18-SWCLOSE-PadSWCLOSED)") (class "Default")
      (node (ref "U$18") (pin "SWCLOSED") (pinfunction "SWCLOSE_SWCLOSED") (pintype "bidirectional"))
    )
    (net (code "82") (name "unconnected-(U$19-SWCLOSE-PadSWCLOSED)") (class "Default")
      (node (ref "U$19") (pin "SWCLOSED") (pinfunction "SWCLOSE_SWCLOSED") (pintype "bidirectional"))
    )
    (net (code "83") (name "unconnected-(U$20-SWCLOSE-PadSWCLOSED)") (class "Default")
      (node (ref "U$20") (pin "SWCLOSED") (pinfunction "SWCLOSE_SWCLOSED") (pintype "bidirectional"))
    )
    (net (code "84") (name "unconnected-(U$21-SWCLOSE-PadSWCLOSED)") (class "Default")
      (node (ref "U$21") (pin "SWCLOSED") (pinfunction "SWCLOSE_SWCLOSED") (pintype "bidirectional"))
    )
    (net (code "85") (name "unconnected-(U$22-SWCLOSE-PadSWCLOSED)") (class "Default")
      (node (ref "U$22") (pin "SWCLOSED") (pinfunction "SWCLOSE_SWCLOSED") (pintype "bidirectional"))
    )
    (net (code "86") (name "unconnected-(U$23-SWCLOSE-PadSWCLOSED)") (class "Default")
      (node (ref "U$23") (pin "SWCLOSED") (pinfunction "SWCLOSE_SWCLOSED") (pintype "bidirectional"))
    )
  )
)
